# noise.net
KiCad netlist of a schematic drawn in EAGLE
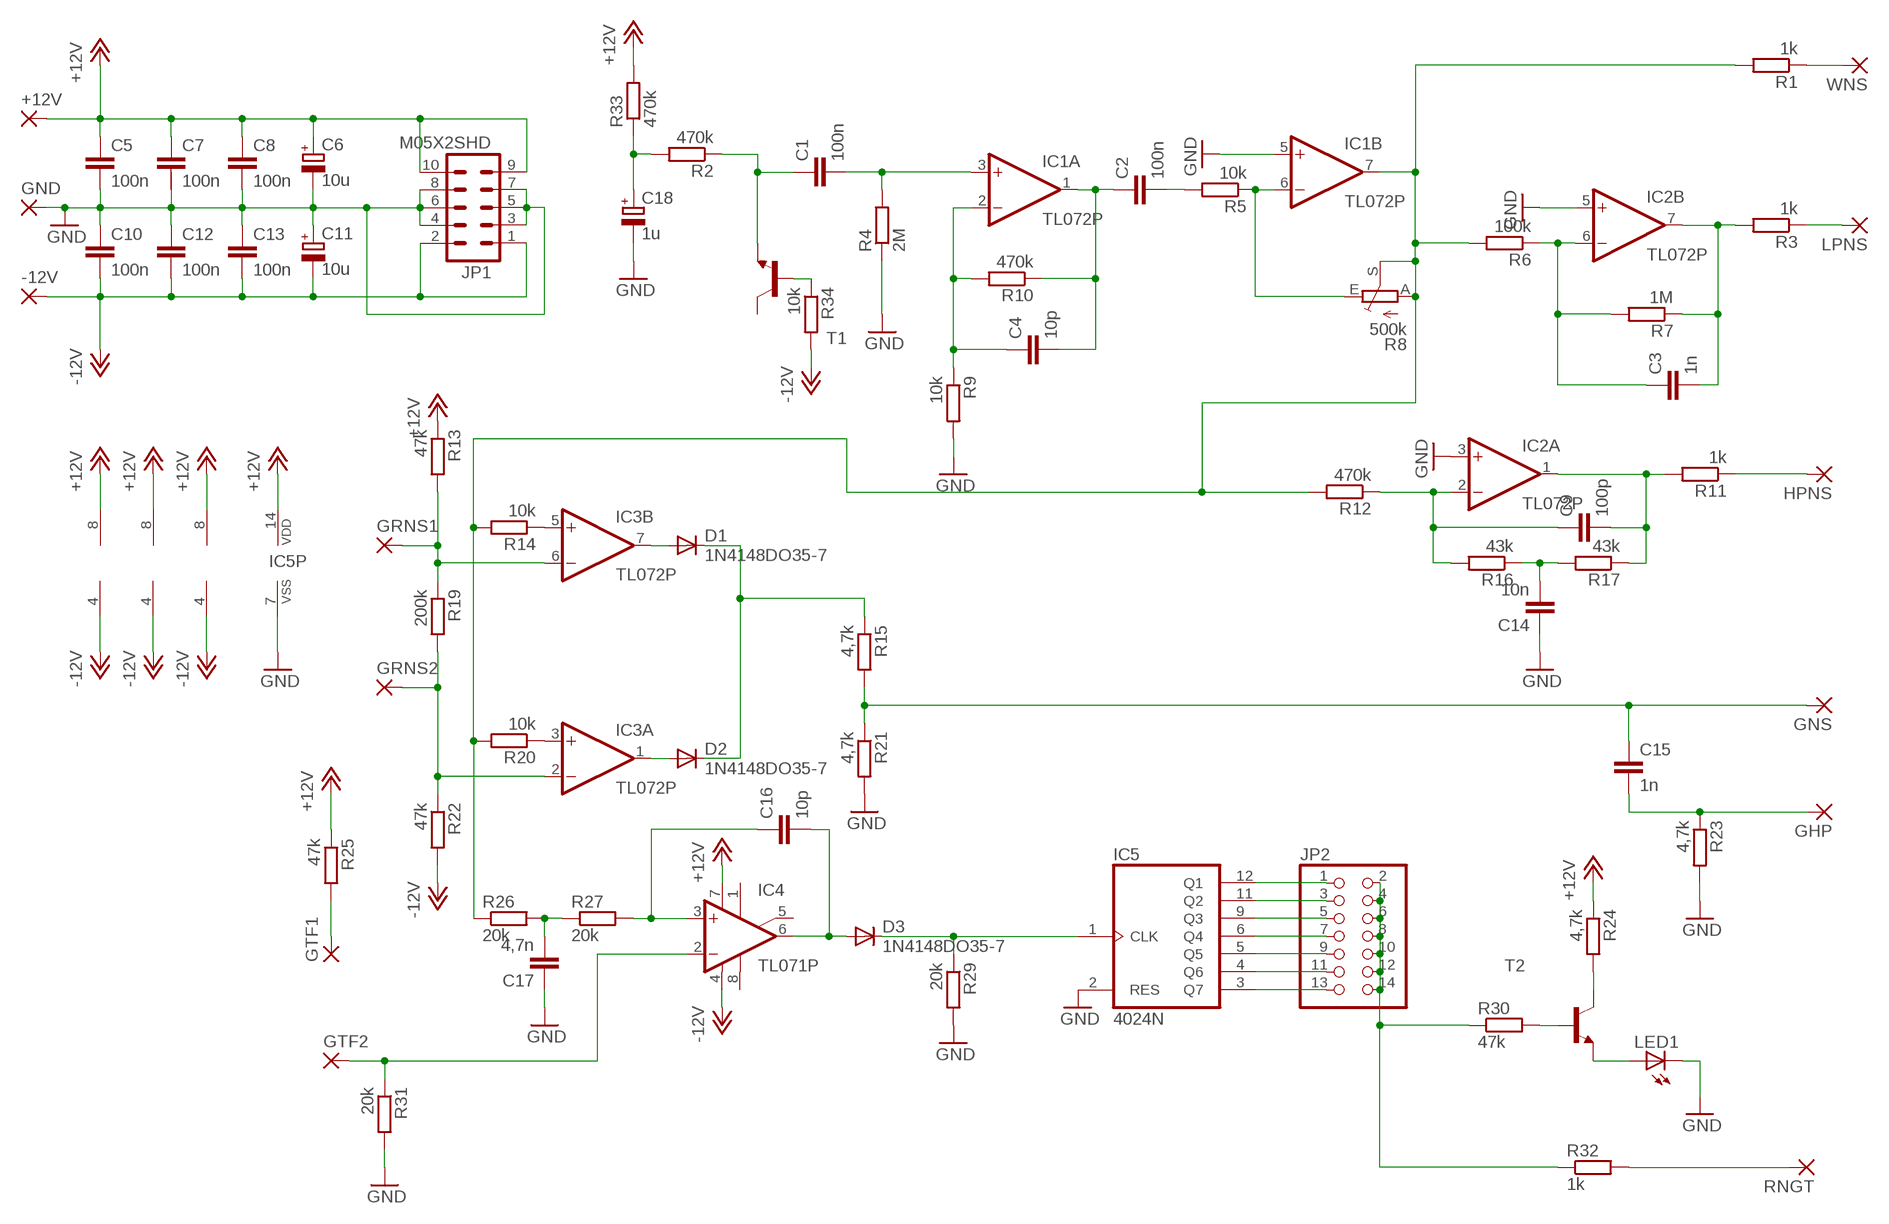
[diagram p0: schematic, sheet 1]

(export (version "E")
  (design (tool "Eeschema 10.0.6"))
  (components
    (comp (ref "+12V")
      (value "2,54/1,0")
      (footprint "eagle-import:2,54_1,0")
      (libsource (lib "eagle-import") (part "2,54/1,0"))
    )
    (comp (ref "-12V")
      (value "2,54/1,0")
      (footprint "eagle-import:2,54_1,0")
      (libsource (lib "eagle-import") (part "2,54/1,0"))
    )
    (comp (ref "C1")
      (value "100n")
      (footprint "eagle-import:C050-035X075")
      (libsource (lib "eagle-import") (part "C-EU050-035X075"))
    )
    (comp (ref "C2")
      (value "100n")
      (footprint "eagle-import:C050-035X075")
      (libsource (lib "eagle-import") (part "C-EU050-035X075"))
    )
    (comp (ref "C3")
      (value "1n")
      (footprint "eagle-import:C050-035X075")
      (libsource (lib "eagle-import") (part "C-EU050-035X075"))
    )
    (comp (ref "C4")
      (value "10p")
      (footprint "eagle-import:C050-035X075")
      (libsource (lib "eagle-import") (part "C-EU050-035X075"))
    )
    (comp (ref "C5")
      (value "100n")
      (footprint "eagle-import:C050-035X075")
      (libsource (lib "eagle-import") (part "C-EU050-035X075"))
    )
    (comp (ref "C6")
      (value "10u")
      (footprint "eagle-import:E2,5-6")
      (libsource (lib "eagle-import") (part "CPOL-EUE2.5-6"))
    )
    (comp (ref "C7")
      (value "100n")
      (footprint "eagle-import:C050-035X075")
      (libsource (lib "eagle-import") (part "C-EU050-035X075"))
    )
    (comp (ref "C8")
      (value "100n")
      (footprint "eagle-import:C050-035X075")
      (libsource (lib "eagle-import") (part "C-EU050-035X075"))
    )
    (comp (ref "C9")
      (value "100p")
      (footprint "eagle-import:C050-035X075")
      (libsource (lib "eagle-import") (part "C-EU050-035X075"))
    )
    (comp (ref "C10")
      (value "100n")
      (footprint "eagle-import:C050-035X075")
      (libsource (lib "eagle-import") (part "C-EU050-035X075"))
    )
    (comp (ref "C11")
      (value "10u")
      (footprint "eagle-import:E2,5-6")
      (libsource (lib "eagle-import") (part "CPOL-EUE2.5-6"))
    )
    (comp (ref "C12")
      (value "100n")
      (footprint "eagle-import:C050-035X075")
      (libsource (lib "eagle-import") (part "C-EU050-035X075"))
    )
    (comp (ref "C13")
      (value "100n")
      (footprint "eagle-import:C050-035X075")
      (libsource (lib "eagle-import") (part "C-EU050-035X075"))
    )
    (comp (ref "C14")
      (value "10n")
      (footprint "eagle-import:C050-035X075")
      (libsource (lib "eagle-import") (part "C-EU050-035X075"))
    )
    (comp (ref "C15")
      (value "1n")
      (footprint "eagle-import:C050-035X075")
      (libsource (lib "eagle-import") (part "C-EU050-035X075"))
    )
    (comp (ref "C16")
      (value "10p")
      (footprint "eagle-import:C050-035X075")
      (libsource (lib "eagle-import") (part "C-EU050-035X075"))
    )
    (comp (ref "C17")
      (value "4,7n")
      (footprint "eagle-import:C050-035X075")
      (libsource (lib "eagle-import") (part "C-EU050-035X075"))
    )
    (comp (ref "C18")
      (value "1u")
      (footprint "eagle-import:E2-5")
      (libsource (lib "eagle-import") (part "CPOL-EUE2-5"))
    )
    (comp (ref "D1")
      (value "1N4148DO35-7")
      (footprint "eagle-import:DO35-7")
      (libsource (lib "eagle-import") (part "1N4148DO35-7"))
    )
    (comp (ref "D2")
      (value "1N4148DO35-7")
      (footprint "eagle-import:DO35-7")
      (libsource (lib "eagle-import") (part "1N4148DO35-7"))
    )
    (comp (ref "D3")
      (value "1N4148DO35-7")
      (footprint "eagle-import:DO35-7")
      (libsource (lib "eagle-import") (part "1N4148DO35-7"))
    )
    (comp (ref "GHP")
      (value "2,54/1,0")
      (footprint "eagle-import:2,54_1,0")
      (libsource (lib "eagle-import") (part "2,54/1,0"))
    )
    (comp (ref "GND")
      (value "2,54/1,0")
      (footprint "eagle-import:2,54_1,0")
      (libsource (lib "eagle-import") (part "2,54/1,0"))
    )
    (comp (ref "GNS")
      (value "2,54/1,0")
      (footprint "eagle-import:2,54_1,0")
      (libsource (lib "eagle-import") (part "2,54/1,0"))
    )
    (comp (ref "GRNS1")
      (value "2,54/1,0")
      (footprint "eagle-import:2,54_1,0")
      (libsource (lib "eagle-import") (part "2,54/1,0"))
    )
    (comp (ref "GRNS2")
      (value "2,54/1,0")
      (footprint "eagle-import:2,54_1,0")
      (libsource (lib "eagle-import") (part "2,54/1,0"))
    )
    (comp (ref "GTF1")
      (value "2,54/1,0")
      (footprint "eagle-import:2,54_1,0")
      (libsource (lib "eagle-import") (part "2,54/1,0"))
    )
    (comp (ref "GTF2")
      (value "2,54/1,0")
      (footprint "eagle-import:2,54_1,0")
      (libsource (lib "eagle-import") (part "2,54/1,0"))
    )
    (comp (ref "HPNS")
      (value "2,54/1,0")
      (footprint "eagle-import:2,54_1,0")
      (libsource (lib "eagle-import") (part "2,54/1,0"))
    )
    (comp (ref "IC1")
      (value "TL072P")
      (footprint "eagle-import:DIL08")
      (libsource (lib "eagle-import") (part "TL072P"))
    )
    (comp (ref "IC2")
      (value "TL072P")
      (footprint "eagle-import:DIL08")
      (libsource (lib "eagle-import") (part "TL072P"))
    )
    (comp (ref "IC3")
      (value "TL072P")
      (footprint "eagle-import:DIL08")
      (libsource (lib "eagle-import") (part "TL072P"))
    )
    (comp (ref "IC4")
      (value "TL071P")
      (footprint "eagle-import:DIL08")
      (libsource (lib "eagle-import") (part "TL071P"))
    )
    (comp (ref "IC5")
      (value "4024N")
      (footprint "eagle-import:DIL14")
      (libsource (lib "eagle-import") (part "4024N"))
    )
    (comp (ref "JP1")
      (value "M05X2SHD")
      (footprint "eagle-import:2X5-SHROUDED")
      (libsource (lib "eagle-import") (part "M05X2SHD"))
    )
    (comp (ref "JP2")
      (value "PINHD-2X7")
      (footprint "eagle-import:2X07")
      (libsource (lib "eagle-import") (part "PINHD-2X7"))
    )
    (comp (ref "LED1")
      (value "LED3MM")
      (footprint "eagle-import:LED3MM")
      (libsource (lib "eagle-import") (part "LED3MM"))
    )
    (comp (ref "LPNS")
      (value "2,54/1,0")
      (footprint "eagle-import:2,54_1,0")
      (libsource (lib "eagle-import") (part "2,54/1,0"))
    )
    (comp (ref "R1")
      (value "1k")
      (footprint "eagle-import:0309_10")
      (libsource (lib "eagle-import") (part "R-EU_0309/10"))
    )
    (comp (ref "R2")
      (value "470k")
      (footprint "eagle-import:0309_10")
      (libsource (lib "eagle-import") (part "R-EU_0309/10"))
    )
    (comp (ref "R3")
      (value "1k")
      (footprint "eagle-import:0309_10")
      (libsource (lib "eagle-import") (part "R-EU_0309/10"))
    )
    (comp (ref "R4")
      (value "2M")
      (footprint "eagle-import:0309_10")
      (libsource (lib "eagle-import") (part "R-EU_0309/10"))
    )
    (comp (ref "R5")
      (value "10k")
      (footprint "eagle-import:0309_10")
      (libsource (lib "eagle-import") (part "R-EU_0309/10"))
    )
    (comp (ref "R6")
      (value "100k")
      (footprint "eagle-import:0309_10")
      (libsource (lib "eagle-import") (part "R-EU_0309/10"))
    )
    (comp (ref "R7")
      (value "1M")
      (footprint "eagle-import:0309_10")
      (libsource (lib "eagle-import") (part "R-EU_0309/10"))
    )
    (comp (ref "R8")
      (value "500k")
      (footprint "eagle-import:RJ9W")
      (libsource (lib "eagle-import") (part "TRIM_EU-RJ9W"))
    )
    (comp (ref "R9")
      (value "10k")
      (footprint "eagle-import:0309_10")
      (libsource (lib "eagle-import") (part "R-EU_0309/10"))
    )
    (comp (ref "R10")
      (value "470k")
      (footprint "eagle-import:0309_10")
      (libsource (lib "eagle-import") (part "R-EU_0309/10"))
    )
    (comp (ref "R11")
      (value "1k")
      (footprint "eagle-import:0309_10")
      (libsource (lib "eagle-import") (part "R-EU_0309/10"))
    )
    (comp (ref "R12")
      (value "470k")
      (footprint "eagle-import:0309_10")
      (libsource (lib "eagle-import") (part "R-EU_0309/10"))
    )
    (comp (ref "R13")
      (value "47k")
      (footprint "eagle-import:0309_10")
      (libsource (lib "eagle-import") (part "R-EU_0309/10"))
    )
    (comp (ref "R14")
      (value "10k")
      (footprint "eagle-import:0309_10")
      (libsource (lib "eagle-import") (part "R-EU_0309/10"))
    )
    (comp (ref "R15")
      (value "4,7k")
      (footprint "eagle-import:0309_10")
      (libsource (lib "eagle-import") (part "R-EU_0309/10"))
    )
    (comp (ref "R16")
      (value "43k")
      (footprint "eagle-import:0309_10")
      (libsource (lib "eagle-import") (part "R-EU_0309/10"))
    )
    (comp (ref "R17")
      (value "43k")
      (footprint "eagle-import:0309_10")
      (libsource (lib "eagle-import") (part "R-EU_0309/10"))
    )
    (comp (ref "R19")
      (value "200k")
      (footprint "eagle-import:0309_10")
      (libsource (lib "eagle-import") (part "R-EU_0309/10"))
    )
    (comp (ref "R20")
      (value "10k")
      (footprint "eagle-import:0309_10")
      (libsource (lib "eagle-import") (part "R-EU_0309/10"))
    )
    (comp (ref "R21")
      (value "4,7k")
      (footprint "eagle-import:0309_10")
      (libsource (lib "eagle-import") (part "R-EU_0309/10"))
    )
    (comp (ref "R22")
      (value "47k")
      (footprint "eagle-import:0309_10")
      (libsource (lib "eagle-import") (part "R-EU_0309/10"))
    )
    (comp (ref "R23")
      (value "4,7k")
      (footprint "eagle-import:0309_10")
      (libsource (lib "eagle-import") (part "R-EU_0309/10"))
    )
    (comp (ref "R24")
      (value "4,7k")
      (footprint "eagle-import:0309_10")
      (libsource (lib "eagle-import") (part "R-EU_0309/10"))
    )
    (comp (ref "R25")
      (value "47k")
      (footprint "eagle-import:0309_10")
      (libsource (lib "eagle-import") (part "R-EU_0309/10"))
    )
    (comp (ref "R26")
      (value "20k")
      (footprint "eagle-import:0309_10")
      (libsource (lib "eagle-import") (part "R-EU_0309/10"))
    )
    (comp (ref "R27")
      (value "20k")
      (footprint "eagle-import:0309_10")
      (libsource (lib "eagle-import") (part "R-EU_0309/10"))
    )
    (comp (ref "R29")
      (value "20k")
      (footprint "eagle-import:0309_10")
      (libsource (lib "eagle-import") (part "R-EU_0309/10"))
    )
    (comp (ref "R30")
      (value "47k")
      (footprint "eagle-import:0309_10")
      (libsource (lib "eagle-import") (part "R-EU_0309/10"))
    )
    (comp (ref "R31")
      (value "20k")
      (footprint "eagle-import:0309_10")
      (libsource (lib "eagle-import") (part "R-EU_0309/10"))
    )
    (comp (ref "R32")
      (value "1k")
      (footprint "eagle-import:0309_10")
      (libsource (lib "eagle-import") (part "R-EU_0309/10"))
    )
    (comp (ref "R33")
      (value "470k")
      (footprint "eagle-import:0309_10")
      (libsource (lib "eagle-import") (part "R-EU_0309/10"))
    )
    (comp (ref "R34")
      (value "10k")
      (footprint "eagle-import:0309_10")
      (libsource (lib "eagle-import") (part "R-EU_0309/10"))
    )
    (comp (ref "RNGT")
      (value "2,54/1,0")
      (footprint "eagle-import:2,54_1,0")
      (libsource (lib "eagle-import") (part "2,54/1,0"))
    )
    (comp (ref "T1")
      (value "2N3904-NPN-TO92-EBC")
      (footprint "eagle-import:TO92-EBC")
      (libsource (lib "eagle-import") (part "-NPN-TO92-EBC2N3904"))
    )
    (comp (ref "T2")
      (value "2N3904-NPN-TO92-EBC")
      (footprint "eagle-import:TO92-EBC")
      (libsource (lib "eagle-import") (part "-NPN-TO92-EBC2N3904"))
    )
    (comp (ref "WNS")
      (value "2,54/1,0")
      (footprint "eagle-import:2,54_1,0")
      (libsource (lib "eagle-import") (part "2,54/1,0"))
    )
  )
  (nets
    (net (code "1") (name "+12V") (class "Default")
      (node (ref "+12V") (pin "1") (pinfunction "P_1") (pintype "passive"))
      (node (ref "C5") (pin "1") (pinfunction "1_1") (pintype "passive"))
      (node (ref "C6") (pin "+") (pinfunction "+_+") (pintype "passive"))
      (node (ref "C7") (pin "1") (pinfunction "1_1") (pintype "passive"))
      (node (ref "C8") (pin "1") (pinfunction "1_1") (pintype "passive"))
      (node (ref "IC1") (pin "8") (pinfunction "V+_8") (pintype "power_in"))
      (node (ref "IC2") (pin "8") (pinfunction "V+_8") (pintype "power_in"))
      (node (ref "IC3") (pin "8") (pinfunction "V+_8") (pintype "power_in"))
      (node (ref "IC4") (pin "7") (pinfunction "V+_7") (pintype "power_in"))
      (node (ref "IC5") (pin "14") (pinfunction "VDD_14") (pintype "power_in"))
      (node (ref "JP1") (pin "10") (pinfunction "10_10") (pintype "passive"))
      (node (ref "JP1") (pin "9") (pinfunction "9_9") (pintype "passive"))
      (node (ref "R13") (pin "1") (pinfunction "1_1") (pintype "passive"))
      (node (ref "R24") (pin "1") (pinfunction "1_1") (pintype "passive"))
      (node (ref "R25") (pin "1") (pinfunction "1_1") (pintype "passive"))
      (node (ref "R33") (pin "2") (pinfunction "2_2") (pintype "passive"))
    )
    (net (code "2") (name "-12V") (class "Default")
      (node (ref "-12V") (pin "1") (pinfunction "P_1") (pintype "passive"))
      (node (ref "C10") (pin "2") (pinfunction "2_2") (pintype "passive"))
      (node (ref "C11") (pin "-") (pinfunction "-_-") (pintype "passive"))
      (node (ref "C12") (pin "2") (pinfunction "2_2") (pintype "passive"))
      (node (ref "C13") (pin "2") (pinfunction "2_2") (pintype "passive"))
      (node (ref "IC1") (pin "4") (pinfunction "V-_4") (pintype "power_in"))
      (node (ref "IC2") (pin "4") (pinfunction "V-_4") (pintype "power_in"))
      (node (ref "IC3") (pin "4") (pinfunction "V-_4") (pintype "power_in"))
      (node (ref "IC4") (pin "4") (pinfunction "V-_4") (pintype "power_in"))
      (node (ref "JP1") (pin "1") (pinfunction "1_1") (pintype "passive"))
      (node (ref "JP1") (pin "2") (pinfunction "2_2") (pintype "passive"))
      (node (ref "R22") (pin "2") (pinfunction "2_2") (pintype "passive"))
      (node (ref "R34") (pin "2") (pinfunction "2_2") (pintype "passive"))
    )
    (net (code "3") (name "GND") (class "Default")
      (node (ref "C10") (pin "1") (pinfunction "1_1") (pintype "passive"))
      (node (ref "C11") (pin "+") (pinfunction "+_+") (pintype "passive"))
      (node (ref "C12") (pin "1") (pinfunction "1_1") (pintype "passive"))
      (node (ref "C13") (pin "1") (pinfunction "1_1") (pintype "passive"))
      (node (ref "C14") (pin "1") (pinfunction "1_1") (pintype "passive"))
      (node (ref "C17") (pin "1") (pinfunction "1_1") (pintype "passive"))
      (node (ref "C18") (pin "-") (pinfunction "-_-") (pintype "passive"))
      (node (ref "C5") (pin "2") (pinfunction "2_2") (pintype "passive"))
      (node (ref "C6") (pin "-") (pinfunction "-_-") (pintype "passive"))
      (node (ref "C7") (pin "2") (pinfunction "2_2") (pintype "passive"))
      (node (ref "C8") (pin "2") (pinfunction "2_2") (pintype "passive"))
      (node (ref "GND") (pin "1") (pinfunction "P_1") (pintype "passive"))
      (node (ref "IC1") (pin "5") (pinfunction "+IN_5") (pintype "input"))
      (node (ref "IC2") (pin "3") (pinfunction "+IN_3") (pintype "input"))
      (node (ref "IC2") (pin "5") (pinfunction "+IN_5") (pintype "input"))
      (node (ref "IC5") (pin "2") (pinfunction "RES_2") (pintype "input"))
      (node (ref "IC5") (pin "7") (pinfunction "VSS_7") (pintype "power_in"))
      (node (ref "JP1") (pin "3") (pinfunction "3_3") (pintype "passive"))
      (node (ref "JP1") (pin "4") (pinfunction "4_4") (pintype "passive"))
      (node (ref "JP1") (pin "5") (pinfunction "5_5") (pintype "passive"))
      (node (ref "JP1") (pin "6") (pinfunction "6_6") (pintype "passive"))
      (node (ref "JP1") (pin "7") (pinfunction "7_7") (pintype "passive"))
      (node (ref "JP1") (pin "8") (pinfunction "8_8") (pintype "passive"))
      (node (ref "LED1") (pin "K") (pinfunction "C_K") (pintype "passive"))
      (node (ref "R21") (pin "2") (pinfunction "2_2") (pintype "passive"))
      (node (ref "R23") (pin "2") (pinfunction "2_2") (pintype "passive"))
      (node (ref "R29") (pin "2") (pinfunction "2_2") (pintype "passive"))
      (node (ref "R31") (pin "2") (pinfunction "2_2") (pintype "passive"))
      (node (ref "R4") (pin "1") (pinfunction "1_1") (pintype "passive"))
      (node (ref "R9") (pin "2") (pinfunction "2_2") (pintype "passive"))
    )
    (net (code "4") (name "Net-(C1-Pad1)") (class "Default")
      (node (ref "C1") (pin "1") (pinfunction "1_1") (pintype "passive"))
      (node (ref "R2") (pin "1") (pinfunction "1_1") (pintype "passive"))
      (node (ref "T1") (pin "E") (pinfunction "E_E") (pintype "passive"))
    )
    (net (code "5") (name "Net-(C2-Pad2)") (class "Default")
      (node (ref "C2") (pin "2") (pinfunction "2_2") (pintype "passive"))
      (node (ref "R5") (pin "2") (pinfunction "2_2") (pintype "passive"))
    )
    (net (code "6") (name "Net-(C14-Pad2)") (class "Default")
      (node (ref "C14") (pin "2") (pinfunction "2_2") (pintype "passive"))
      (node (ref "R16") (pin "1") (pinfunction "1_1") (pintype "passive"))
      (node (ref "R17") (pin "2") (pinfunction "2_2") (pintype "passive"))
    )
    (net (code "7") (name "Net-(C17-Pad2)") (class "Default")
      (node (ref "C17") (pin "2") (pinfunction "2_2") (pintype "passive"))
      (node (ref "R26") (pin "2") (pinfunction "2_2") (pintype "passive"))
      (node (ref "R27") (pin "1") (pinfunction "1_1") (pintype "passive"))
    )
    (net (code "8") (name "Net-(C18-Pad+)") (class "Default")
      (node (ref "C18") (pin "+") (pinfunction "+_+") (pintype "passive"))
      (node (ref "R2") (pin "2") (pinfunction "2_2") (pintype "passive"))
      (node (ref "R33") (pin "1") (pinfunction "1_1") (pintype "passive"))
    )
    (net (code "9") (name "Net-(D1-PadC)") (class "Default")
      (node (ref "D1") (pin "C") (pinfunction "C_C") (pintype "passive"))
      (node (ref "D2") (pin "C") (pinfunction "C_C") (pintype "passive"))
      (node (ref "R15") (pin "1") (pinfunction "1_1") (pintype "passive"))
    )
    (net (code "10") (name "Net-(GHP-P)") (class "Default")
      (node (ref "C15") (pin "2") (pinfunction "2_2") (pintype "passive"))
      (node (ref "GHP") (pin "1") (pinfunction "P_1") (pintype "passive"))
      (node (ref "R23") (pin "1") (pinfunction "1_1") (pintype "passive"))
    )
    (net (code "11") (name "Net-(GNS-P)") (class "Default")
      (node (ref "C15") (pin "1") (pinfunction "1_1") (pintype "passive"))
      (node (ref "GNS") (pin "1") (pinfunction "P_1") (pintype "passive"))
      (node (ref "R15") (pin "2") (pinfunction "2_2") (pintype "passive"))
      (node (ref "R21") (pin "1") (pinfunction "1_1") (pintype "passive"))
    )
    (net (code "12") (name "Net-(GRNS1-P)") (class "Default")
      (node (ref "GRNS1") (pin "1") (pinfunction "P_1") (pintype "passive"))
      (node (ref "IC3") (pin "6") (pinfunction "-IN_6") (pintype "input"))
      (node (ref "R13") (pin "2") (pinfunction "2_2") (pintype "passive"))
      (node (ref "R19") (pin "1") (pinfunction "1_1") (pintype "passive"))
    )
    (net (code "13") (name "Net-(GRNS2-P)") (class "Default")
      (node (ref "GRNS2") (pin "1") (pinfunction "P_1") (pintype "passive"))
      (node (ref "IC3") (pin "2") (pinfunction "-IN_2") (pintype "input"))
      (node (ref "R19") (pin "2") (pinfunction "2_2") (pintype "passive"))
      (node (ref "R22") (pin "1") (pinfunction "1_1") (pintype "passive"))
    )
    (net (code "14") (name "Net-(GTF1-P)") (class "Default")
      (node (ref "GTF1") (pin "1") (pinfunction "P_1") (pintype "passive"))
      (node (ref "R25") (pin "2") (pinfunction "2_2") (pintype "passive"))
    )
    (net (code "15") (name "Net-(GTF2-P)") (class "Default")
      (node (ref "GTF2") (pin "1") (pinfunction "P_1") (pintype "passive"))
      (node (ref "IC4") (pin "2") (pinfunction "-IN_2") (pintype "input"))
      (node (ref "R31") (pin "1") (pinfunction "1_1") (pintype "passive"))
    )
    (net (code "16") (name "Net-(HPNS-P)") (class "Default")
      (node (ref "HPNS") (pin "1") (pinfunction "P_1") (pintype "passive"))
      (node (ref "R11") (pin "1") (pinfunction "1_1") (pintype "passive"))
    )
    (net (code "17") (name "Net-(IC1A-+IN)") (class "Default")
      (node (ref "C1") (pin "2") (pinfunction "2_2") (pintype "passive"))
      (node (ref "IC1") (pin "3") (pinfunction "+IN_3") (pintype "input"))
      (node (ref "R4") (pin "2") (pinfunction "2_2") (pintype "passive"))
    )
    (net (code "18") (name "Net-(IC1A--IN)") (class "Default")
      (node (ref "C4") (pin "1") (pinfunction "1_1") (pintype "passive"))
      (node (ref "IC1") (pin "2") (pinfunction "-IN_2") (pintype "input"))
      (node (ref "R10") (pin "2") (pinfunction "2_2") (pintype "passive"))
      (node (ref "R9") (pin "1") (pinfunction "1_1") (pintype "passive"))
    )
    (net (code "19") (name "Net-(IC1A-OUT)") (class "Default")
      (node (ref "C2") (pin "1") (pinfunction "1_1") (pintype "passive"))
      (node (ref "C4") (pin "2") (pinfunction "2_2") (pintype "passive"))
      (node (ref "IC1") (pin "1") (pinfunction "OUT_1") (pintype "output"))
      (node (ref "R10") (pin "1") (pinfunction "1_1") (pintype "passive"))
    )
    (net (code "20") (name "Net-(IC1B--IN)") (class "Default")
      (node (ref "IC1") (pin "6") (pinfunction "-IN_6") (pintype "input"))
      (node (ref "R5") (pin "1") (pinfunction "1_1") (pintype "passive"))
      (node (ref "R8") (pin "E") (pinfunction "E_E") (pintype "passive"))
    )
    (net (code "21") (name "Net-(IC1B-OUT)") (class "Default")
      (node (ref "IC1") (pin "7") (pinfunction "OUT_7") (pintype "output"))
      (node (ref "R1") (pin "2") (pinfunction "2_2") (pintype "passive"))
      (node (ref "R12") (pin "2") (pinfunction "2_2") (pintype "passive"))
      (node (ref "R14") (pin "2") (pinfunction "2_2") (pintype "passive"))
      (node (ref "R20") (pin "2") (pinfunction "2_2") (pintype "passive"))
      (node (ref "R26") (pin "1") (pinfunction "1_1") (pintype "passive"))
      (node (ref "R6") (pin "2") (pinfunction "2_2") (pintype "passive"))
      (node (ref "R8") (pin "A") (pinfunction "A_A") (pintype "passive"))
      (node (ref "R8") (pin "S") (pinfunction "S_S") (pintype "passive"))
    )
    (net (code "22") (name "Net-(IC2A--IN)") (class "Default")
      (node (ref "C9") (pin "1") (pinfunction "1_1") (pintype "passive"))
      (node (ref "IC2") (pin "2") (pinfunction "-IN_2") (pintype "input"))
      (node (ref "R12") (pin "1") (pinfunction "1_1") (pintype "passive"))
      (node (ref "R16") (pin "2") (pinfunction "2_2") (pintype "passive"))
    )
    (net (code "23") (name "Net-(IC2A-OUT)") (class "Default")
      (node (ref "C9") (pin "2") (pinfunction "2_2") (pintype "passive"))
      (node (ref "IC2") (pin "1") (pinfunction "OUT_1") (pintype "output"))
      (node (ref "R11") (pin "2") (pinfunction "2_2") (pintype "passive"))
      (node (ref "R17") (pin "1") (pinfunction "1_1") (pintype "passive"))
    )
    (net (code "24") (name "Net-(IC2B--IN)") (class "Default")
      (node (ref "C3") (pin "1") (pinfunction "1_1") (pintype "passive"))
      (node (ref "IC2") (pin "6") (pinfunction "-IN_6") (pintype "input"))
      (node (ref "R6") (pin "1") (pinfunction "1_1") (pintype "passive"))
      (node (ref "R7") (pin "2") (pinfunction "2_2") (pintype "passive"))
    )
    (net (code "25") (name "Net-(IC2B-OUT)") (class "Default")
      (node (ref "C3") (pin "2") (pinfunction "2_2") (pintype "passive"))
      (node (ref "IC2") (pin "7") (pinfunction "OUT_7") (pintype "output"))
      (node (ref "R3") (pin "2") (pinfunction "2_2") (pintype "passive"))
      (node (ref "R7") (pin "1") (pinfunction "1_1") (pintype "passive"))
    )
    (net (code "26") (name "Net-(IC3A-+IN)") (class "Default")
      (node (ref "IC3") (pin "3") (pinfunction "+IN_3") (pintype "input"))
      (node (ref "R20") (pin "1") (pinfunction "1_1") (pintype "passive"))
    )
    (net (code "27") (name "Net-(IC3A-OUT)") (class "Default")
      (node (ref "D2") (pin "A") (pinfunction "A_A") (pintype "passive"))
      (node (ref "IC3") (pin "1") (pinfunction "OUT_1") (pintype "output"))
    )
    (net (code "28") (name "Net-(IC3B-+IN)") (class "Default")
      (node (ref "IC3") (pin "5") (pinfunction "+IN_5") (pintype "input"))
      (node (ref "R14") (pin "1") (pinfunction "1_1") (pintype "passive"))
    )
    (net (code "29") (name "Net-(IC3B-OUT)") (class "Default")
      (node (ref "D1") (pin "A") (pinfunction "A_A") (pintype "passive"))
      (node (ref "IC3") (pin "7") (pinfunction "OUT_7") (pintype "output"))
    )
    (net (code "30") (name "Net-(IC4-+IN)") (class "Default")
      (node (ref "C16") (pin "1") (pinfunction "1_1") (pintype "passive"))
      (node (ref "IC4") (pin "3") (pinfunction "+IN_3") (pintype "input"))
      (node (ref "R27") (pin "2") (pinfunction "2_2") (pintype "passive"))
    )
    (net (code "31") (name "Net-(IC4-OUT)") (class "Default")
      (node (ref "C16") (pin "2") (pinfunction "2_2") (pintype "passive"))
      (node (ref "D3") (pin "A") (pinfunction "A_A") (pintype "passive"))
      (node (ref "IC4") (pin "6") (pinfunction "OUT_6") (pintype "output"))
    )
    (net (code "32") (name "Net-(IC5A-CLK)") (class "Default")
      (node (ref "D3") (pin "C") (pinfunction "C_C") (pintype "passive"))
      (node (ref "IC5") (pin "1") (pinfunction "CLK_1") (pintype "input"))
      (node (ref "R29") (pin "1") (pinfunction "1_1") (pintype "passive"))
    )
    (net (code "33") (name "Net-(IC5A-Q1)") (class "Default")
      (node (ref "IC5") (pin "12") (pinfunction "Q1_12") (pintype "output"))
      (node (ref "JP2") (pin "1") (pinfunction "1_1") (pintype "passive"))
    )
    (net (code "34") (name "Net-(IC5A-Q2)") (class "Default")
      (node (ref "IC5") (pin "11") (pinfunction "Q2_11") (pintype "output"))
      (node (ref "JP2") (pin "3") (pinfunction "3_3") (pintype "passive"))
    )
    (net (code "35") (name "Net-(IC5A-Q3)") (class "Default")
      (node (ref "IC5") (pin "9") (pinfunction "Q3_9") (pintype "output"))
      (node (ref "JP2") (pin "5") (pinfunction "5_5") (pintype "passive"))
    )
    (net (code "36") (name "Net-(IC5A-Q4)") (class "Default")
      (node (ref "IC5") (pin "6") (pinfunction "Q4_6") (pintype "output"))
      (node (ref "JP2") (pin "7") (pinfunction "7_7") (pintype "passive"))
    )
    (net (code "37") (name "Net-(IC5A-Q5)") (class "Default")
      (node (ref "IC5") (pin "5") (pinfunction "Q5_5") (pintype "output"))
      (node (ref "JP2") (pin "9") (pinfunction "9_9") (pintype "passive"))
    )
    (net (code "38") (name "Net-(IC5A-Q6)") (class "Default")
      (node (ref "IC5") (pin "4") (pinfunction "Q6_4") (pintype "output"))
      (node (ref "JP2") (pin "11") (pinfunction "11_11") (pintype "passive"))
    )
    (net (code "39") (name "Net-(IC5A-Q7)") (class "Default")
      (node (ref "IC5") (pin "3") (pinfunction "Q7_3") (pintype "output"))
      (node (ref "JP2") (pin "13") (pinfunction "13_13") (pintype "passive"))
    )
    (net (code "40") (name "Net-(JP2-Pad10)") (class "Default")
      (node (ref "JP2") (pin "10") (pinfunction "10_10") (pintype "passive"))
      (node (ref "JP2") (pin "12") (pinfunction "12_12") (pintype "passive"))
      (node (ref "JP2") (pin "14") (pinfunction "14_14") (pintype "passive"))
      (node (ref "JP2") (pin "2") (pinfunction "2_2") (pintype "passive"))
      (node (ref "JP2") (pin "4") (pinfunction "4_4") (pintype "passive"))
      (node (ref "JP2") (pin "6") (pinfunction "6_6") (pintype "passive"))
      (node (ref "JP2") (pin "8") (pinfunction "8_8") (pintype "passive"))
      (node (ref "R30") (pin "1") (pinfunction "1_1") (pintype "passive"))
      (node (ref "R32") (pin "1") (pinfunction "1_1") (pintype "passive"))
    )
    (net (code "41") (name "Net-(LED1-PadA)") (class "Default")
      (node (ref "LED1") (pin "A") (pinfunction "A_A") (pintype "passive"))
      (node (ref "T2") (pin "E") (pinfunction "E_E") (pintype "passive"))
    )
    (net (code "42") (name "Net-(LPNS-P)") (class "Default")
      (node (ref "LPNS") (pin "1") (pinfunction "P_1") (pintype "passive"))
      (node (ref "R3") (pin "1") (pinfunction "1_1") (pintype "passive"))
    )
    (net (code "43") (name "Net-(R24-Pad2)") (class "Default")
      (node (ref "R24") (pin "2") (pinfunction "2_2") (pintype "passive"))
      (node (ref "T2") (pin "C") (pinfunction "C_C") (pintype "passive"))
    )
    (net (code "44") (name "Net-(R30-Pad2)") (class "Default")
      (node (ref "R30") (pin "2") (pinfunction "2_2") (pintype "passive"))
      (node (ref "T2") (pin "B") (pinfunction "B_B") (pintype "passive"))
    )
    (net (code "45") (name "Net-(R34-Pad1)") (class "Default")
      (node (ref "R34") (pin "1") (pinfunction "1_1") (pintype "passive"))
      (node (ref "T1") (pin "B") (pinfunction "B_B") (pintype "passive"))
    )
    (net (code "46") (name "Net-(RNGT-P)") (class "Default")
      (node (ref "R32") (pin "2") (pinfunction "2_2") (pintype "passive"))
      (node (ref "RNGT") (pin "1") (pinfunction "P_1") (pintype "passive"))
    )
    (net (code "47") (name "Net-(WNS-P)") (class "Default")
      (node (ref "R1") (pin "1") (pinfunction "1_1") (pintype "passive"))
      (node (ref "WNS") (pin "1") (pinfunction "P_1") (pintype "passive"))
    )
    (net (code "48") (name "unconnected-(IC4-ON1-Pad1)") (class "Default")
      (node (ref "IC4") (pin "1") (pinfunction "ON1_1") (pintype "passive"))
    )
    (net (code "49") (name "unconnected-(IC4-ON2-Pad5)") (class "Default")
      (node (ref "IC4") (pin "5") (pinfunction "ON2_5") (pintype "passive"))
    )
    (net (code "50") (name "unconnected-(IC4-OPT-Pad8)") (class "Default")
      (node (ref "IC4") (pin "8") (pinfunction "OPT_8") (pintype "passive"))
    )
    (net (code "51") (name "unconnected-(T1-PadC)") (class "Default")
      (node (ref "T1") (pin "C") (pinfunction "C_C") (pintype "passive"))
    )
  )
)
